# room_ind.net
KiCad netlist of a schematic drawn in EAGLE
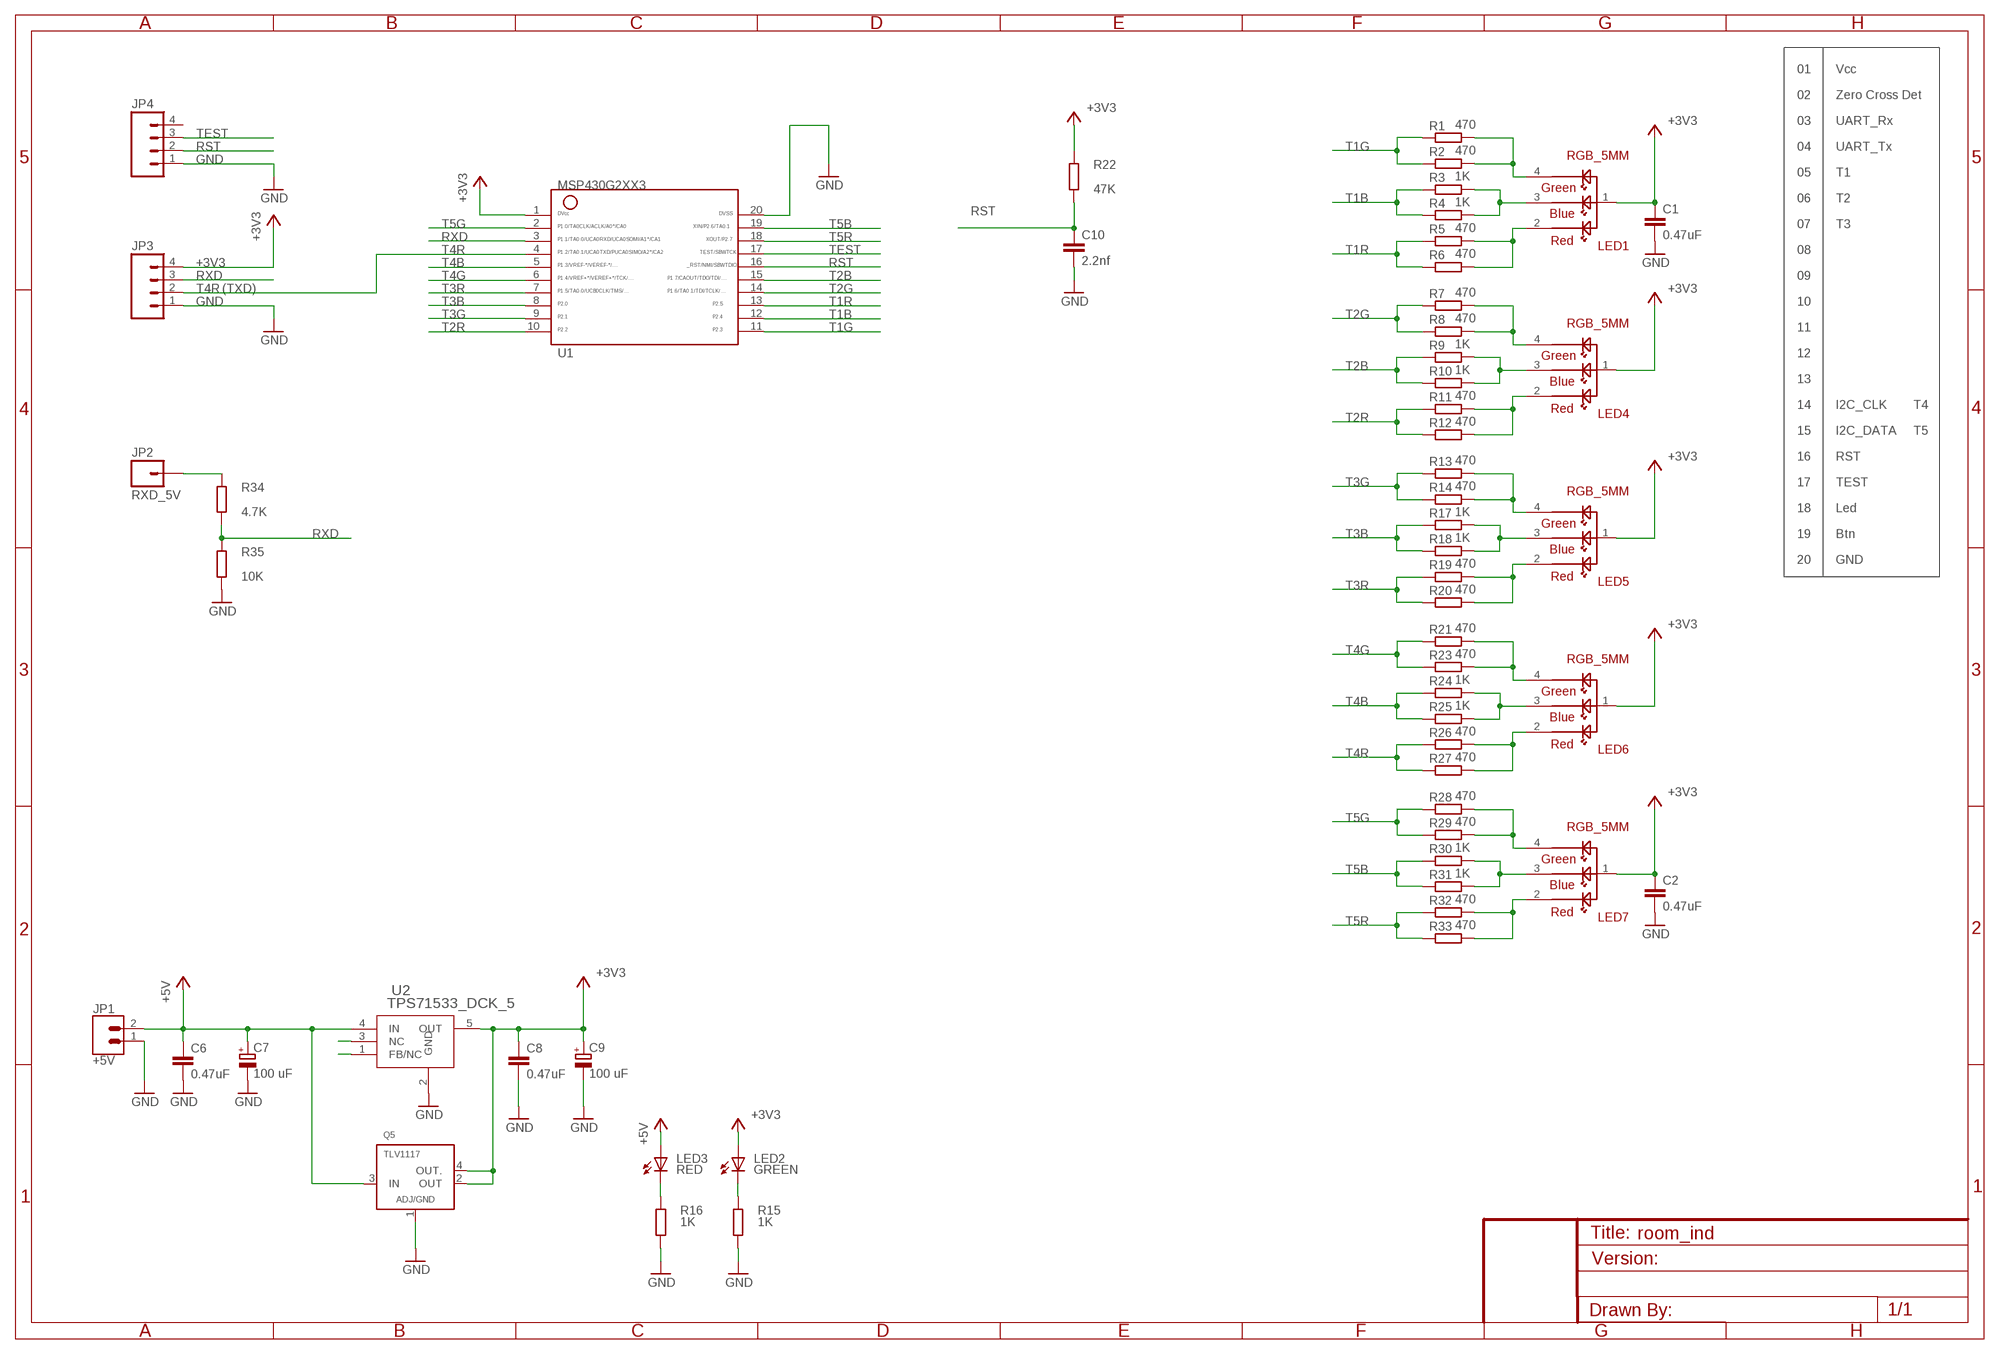
[diagram p0: schematic, sheet 1]

(export (version "E")
  (design (tool "Eeschema 10.0.6"))
  (components
    (comp (ref "C1")
      (value "0.47uF")
      (footprint "eagle-import:C0805")
      (libsource (lib "eagle-import") (part "C-EUC0805"))
    )
    (comp (ref "C2")
      (value "0.47uF")
      (footprint "eagle-import:C0805")
      (libsource (lib "eagle-import") (part "C-EUC0805"))
    )
    (comp (ref "C6")
      (value "0.47uF")
      (footprint "eagle-import:C0805")
      (libsource (lib "eagle-import") (part "C-EUC0805"))
    )
    (comp (ref "C7")
      (value "100 uF")
      (footprint "eagle-import:E2,5-7")
      (libsource (lib "eagle-import") (part "CPOL-EUE2.5-7"))
    )
    (comp (ref "C8")
      (value "0.47uF")
      (footprint "eagle-import:C0805")
      (libsource (lib "eagle-import") (part "C-EUC0805"))
    )
    (comp (ref "C9")
      (value "100 uF")
      (footprint "eagle-import:E2,5-7")
      (libsource (lib "eagle-import") (part "CPOL-EUE2.5-7"))
    )
    (comp (ref "C10")
      (value "2.2nf")
      (footprint "eagle-import:C0805")
      (libsource (lib "eagle-import") (part "C-EUC0805"))
    )
    (comp (ref "JP1")
      (value "+5V")
      (footprint "eagle-import:BLUE_TERM")
      (libsource (lib "eagle-import") (part "BLUE_TERM"))
    )
    (comp (ref "JP2")
      (value "RXD_5V")
      (footprint "eagle-import:1X01")
      (libsource (lib "eagle-import") (part "M01PTH"))
    )
    (comp (ref "JP3")
      (value "M04PTH")
      (footprint "eagle-import:1X04")
      (libsource (lib "eagle-import") (part "M04PTH"))
    )
    (comp (ref "JP4")
      (value "M04PTH")
      (footprint "eagle-import:1X04")
      (libsource (lib "eagle-import") (part "M04PTH"))
    )
    (comp (ref "LED1")
      (value "RGB_5MM")
      (footprint "eagle-import:RGB_5MM")
      (libsource (lib "eagle-import") (part "RGB_5MM"))
    )
    (comp (ref "LED2")
      (value "GREEN")
      (footprint "eagle-import:CHIP-LED0805")
      (libsource (lib "eagle-import") (part "LEDCHIP-LED0805"))
    )
    (comp (ref "LED3")
      (value "RED")
      (footprint "eagle-import:CHIP-LED0805")
      (libsource (lib "eagle-import") (part "LEDCHIP-LED0805"))
    )
    (comp (ref "LED4")
      (value "RGB_5MM")
      (footprint "eagle-import:RGB_5MM")
      (libsource (lib "eagle-import") (part "RGB_5MM"))
    )
    (comp (ref "LED5")
      (value "RGB_5MM")
      (footprint "eagle-import:RGB_5MM")
      (libsource (lib "eagle-import") (part "RGB_5MM"))
    )
    (comp (ref "LED6")
      (value "RGB_5MM")
      (footprint "eagle-import:RGB_5MM")
      (libsource (lib "eagle-import") (part "RGB_5MM"))
    )
    (comp (ref "LED7")
      (value "RGB_5MM")
      (footprint "eagle-import:RGB_5MM")
      (libsource (lib "eagle-import") (part "RGB_5MM"))
    )
    (comp (ref "Q5")
      (value "TLV1117")
      (footprint "eagle-import:SOT223-4")
      (libsource (lib "eagle-import") (part "TLV1117"))
    )
    (comp (ref "R1")
      (value "470")
      (footprint "eagle-import:R0805")
      (libsource (lib "eagle-import") (part "R-EU_R0805"))
    )
    (comp (ref "R2")
      (value "470")
      (footprint "eagle-import:0207_7")
      (libsource (lib "eagle-import") (part "R-EU_0207/7"))
    )
    (comp (ref "R3")
      (value "1K")
      (footprint "eagle-import:R0805")
      (libsource (lib "eagle-import") (part "R-EU_R0805"))
    )
    (comp (ref "R4")
      (value "1K")
      (footprint "eagle-import:0207_7")
      (libsource (lib "eagle-import") (part "R-EU_0207/7"))
    )
    (comp (ref "R5")
      (value "470")
      (footprint "eagle-import:R0805")
      (libsource (lib "eagle-import") (part "R-EU_R0805"))
    )
    (comp (ref "R6")
      (value "470")
      (footprint "eagle-import:0207_7")
      (libsource (lib "eagle-import") (part "R-EU_0207/7"))
    )
    (comp (ref "R7")
      (value "470")
      (footprint "eagle-import:R0805")
      (libsource (lib "eagle-import") (part "R-EU_R0805"))
    )
    (comp (ref "R8")
      (value "470")
      (footprint "eagle-import:0207_7")
      (libsource (lib "eagle-import") (part "R-EU_0207/7"))
    )
    (comp (ref "R9")
      (value "1K")
      (footprint "eagle-import:R0805")
      (libsource (lib "eagle-import") (part "R-EU_R0805"))
    )
    (comp (ref "R10")
      (value "1K")
      (footprint "eagle-import:0207_7")
      (libsource (lib "eagle-import") (part "R-EU_0207/7"))
    )
    (comp (ref "R11")
      (value "470")
      (footprint "eagle-import:R0805")
      (libsource (lib "eagle-import") (part "R-EU_R0805"))
    )
    (comp (ref "R12")
      (value "470")
      (footprint "eagle-import:0207_7")
      (libsource (lib "eagle-import") (part "R-EU_0207/7"))
    )
    (comp (ref "R13")
      (value "470")
      (footprint "eagle-import:R0805")
      (libsource (lib "eagle-import") (part "R-EU_R0805"))
    )
    (comp (ref "R14")
      (value "470")
      (footprint "eagle-import:0207_7")
      (libsource (lib "eagle-import") (part "R-EU_0207/7"))
    )
    (comp (ref "R15")
      (value "1K")
      (footprint "eagle-import:R0805")
      (libsource (lib "eagle-import") (part "R-EU_R0805"))
    )
    (comp (ref "R16")
      (value "1K")
      (footprint "eagle-import:R0805")
      (libsource (lib "eagle-import") (part "R-EU_R0805"))
    )
    (comp (ref "R17")
      (value "1K")
      (footprint "eagle-import:R0805")
      (libsource (lib "eagle-import") (part "R-EU_R0805"))
    )
    (comp (ref "R18")
      (value "1K")
      (footprint "eagle-import:0207_7")
      (libsource (lib "eagle-import") (part "R-EU_0207/7"))
    )
    (comp (ref "R19")
      (value "470")
      (footprint "eagle-import:R0805")
      (libsource (lib "eagle-import") (part "R-EU_R0805"))
    )
    (comp (ref "R20")
      (value "470")
      (footprint "eagle-import:0207_7")
      (libsource (lib "eagle-import") (part "R-EU_0207/7"))
    )
    (comp (ref "R21")
      (value "470")
      (footprint "eagle-import:R0805")
      (libsource (lib "eagle-import") (part "R-EU_R0805"))
    )
    (comp (ref "R22")
      (value "47K")
      (footprint "eagle-import:R0805")
      (libsource (lib "eagle-import") (part "R-EU_R0805"))
    )
    (comp (ref "R23")
      (value "470")
      (footprint "eagle-import:0207_7")
      (libsource (lib "eagle-import") (part "R-EU_0207/7"))
    )
    (comp (ref "R24")
      (value "1K")
      (footprint "eagle-import:R0805")
      (libsource (lib "eagle-import") (part "R-EU_R0805"))
    )
    (comp (ref "R25")
      (value "1K")
      (footprint "eagle-import:0207_7")
      (libsource (lib "eagle-import") (part "R-EU_0207/7"))
    )
    (comp (ref "R26")
      (value "470")
      (footprint "eagle-import:R0805")
      (libsource (lib "eagle-import") (part "R-EU_R0805"))
    )
    (comp (ref "R27")
      (value "470")
      (footprint "eagle-import:0207_7")
      (libsource (lib "eagle-import") (part "R-EU_0207/7"))
    )
    (comp (ref "R28")
      (value "470")
      (footprint "eagle-import:R0805")
      (libsource (lib "eagle-import") (part "R-EU_R0805"))
    )
    (comp (ref "R29")
      (value "470")
      (footprint "eagle-import:0207_7")
      (libsource (lib "eagle-import") (part "R-EU_0207/7"))
    )
    (comp (ref "R30")
      (value "1K")
      (footprint "eagle-import:R0805")
      (libsource (lib "eagle-import") (part "R-EU_R0805"))
    )
    (comp (ref "R31")
      (value "1K")
      (footprint "eagle-import:0207_7")
      (libsource (lib "eagle-import") (part "R-EU_0207/7"))
    )
    (comp (ref "R32")
      (value "470")
      (footprint "eagle-import:R0805")
      (libsource (lib "eagle-import") (part "R-EU_R0805"))
    )
    (comp (ref "R33")
      (value "470")
      (footprint "eagle-import:0207_7")
      (libsource (lib "eagle-import") (part "R-EU_0207/7"))
    )
    (comp (ref "R34")
      (value "4.7K")
      (footprint "eagle-import:R0805")
      (libsource (lib "eagle-import") (part "R-EU_R0805"))
    )
    (comp (ref "R35")
      (value "10K")
      (footprint "eagle-import:R0805")
      (libsource (lib "eagle-import") (part "R-EU_R0805"))
    )
    (comp (ref "U1")
      (value "G2XX3---PW20")
      (footprint "eagle-import:PW20")
      (libsource (lib "eagle-import") (part "G2XX3---PW20"))
    )
    (comp (ref "U2")
      (value "TPS71533_DCK_5")
      (footprint "eagle-import:DCK5")
      (fields
        (field (name "GENERIC_PART_NUMBER") "TPS71533")
        (field (name "MANUFACTURER") "Texas Instruments")
        (field (name "MANUFACTURER_PART_NUMBER") "tps71533_dck_5")
      )
      (libsource (lib "eagle-import") (part "TPS71533_DCK_5"))
    )
  )
  (nets
    (net (code "1") (name "+3V3") (class "Default")
      (node (ref "C1") (pin "1") (pinfunction "1_1") (pintype "passive"))
      (node (ref "C2") (pin "1") (pinfunction "1_1") (pintype "passive"))
      (node (ref "C8") (pin "1") (pinfunction "1_1") (pintype "passive"))
      (node (ref "C9") (pin "+") (pinfunction "+_+") (pintype "passive"))
      (node (ref "JP3") (pin "4") (pinfunction "4_4") (pintype "passive"))
      (node (ref "LED1") (pin "1") (pinfunction "1_1") (pintype "bidirectional"))
      (node (ref "LED2") (pin "A") (pinfunction "A_A") (pintype "passive"))
      (node (ref "LED4") (pin "1") (pinfunction "1_1") (pintype "bidirectional"))
      (node (ref "LED5") (pin "1") (pinfunction "1_1") (pintype "bidirectional"))
      (node (ref "LED6") (pin "1") (pinfunction "1_1") (pintype "bidirectional"))
      (node (ref "LED7") (pin "1") (pinfunction "1_1") (pintype "bidirectional"))
      (node (ref "Q5") (pin "2") (pinfunction "OUT_2") (pintype "power_in"))
      (node (ref "Q5") (pin "4") (pinfunction "OUT._4") (pintype "power_in"))
      (node (ref "R22") (pin "2") (pinfunction "2_2") (pintype "passive"))
      (node (ref "U1") (pin "1") (pinfunction "1_1") (pintype "bidirectional"))
      (node (ref "U2") (pin "5") (pinfunction "OUT_5") (pintype "power_in"))
    )
    (net (code "2") (name "+5V") (class "Default")
      (node (ref "C6") (pin "1") (pinfunction "1_1") (pintype "passive"))
      (node (ref "C7") (pin "+") (pinfunction "+_+") (pintype "passive"))
      (node (ref "JP1") (pin "2") (pinfunction "2_2") (pintype "passive"))
      (node (ref "LED3") (pin "A") (pinfunction "A_A") (pintype "passive"))
      (node (ref "Q5") (pin "3") (pinfunction "IN_3") (pintype "power_in"))
      (node (ref "U2") (pin "4") (pinfunction "IN_4") (pintype "power_in"))
    )
    (net (code "3") (name "/RST") (class "Default")
      (node (ref "C10") (pin "1") (pinfunction "1_1") (pintype "passive"))
      (node (ref "JP4") (pin "2") (pinfunction "2_2") (pintype "passive"))
      (node (ref "R22") (pin "1") (pinfunction "1_1") (pintype "passive"))
      (node (ref "U1") (pin "16") (pinfunction "16_16") (pintype "bidirectional"))
    )
    (net (code "4") (name "/RXD") (class "Default")
      (node (ref "JP3") (pin "3") (pinfunction "3_3") (pintype "passive"))
      (node (ref "R34") (pin "1") (pinfunction "1_1") (pintype "passive"))
      (node (ref "R35") (pin "2") (pinfunction "2_2") (pintype "passive"))
      (node (ref "U1") (pin "3") (pinfunction "3_3") (pintype "bidirectional"))
    )
    (net (code "5") (name "/T1B") (class "Default")
      (node (ref "R3") (pin "1") (pinfunction "1_1") (pintype "passive"))
      (node (ref "R4") (pin "1") (pinfunction "1_1") (pintype "passive"))
      (node (ref "U1") (pin "12") (pinfunction "12_12") (pintype "bidirectional"))
    )
    (net (code "6") (name "/T1G") (class "Default")
      (node (ref "R1") (pin "1") (pinfunction "1_1") (pintype "passive"))
      (node (ref "R2") (pin "1") (pinfunction "1_1") (pintype "passive"))
      (node (ref "U1") (pin "11") (pinfunction "11_11") (pintype "bidirectional"))
    )
    (net (code "7") (name "/T1R") (class "Default")
      (node (ref "R5") (pin "1") (pinfunction "1_1") (pintype "passive"))
      (node (ref "R6") (pin "1") (pinfunction "1_1") (pintype "passive"))
      (node (ref "U1") (pin "13") (pinfunction "13_13") (pintype "bidirectional"))
    )
    (net (code "8") (name "/T2B") (class "Default")
      (node (ref "R10") (pin "1") (pinfunction "1_1") (pintype "passive"))
      (node (ref "R9") (pin "1") (pinfunction "1_1") (pintype "passive"))
      (node (ref "U1") (pin "15") (pinfunction "15_15") (pintype "bidirectional"))
    )
    (net (code "9") (name "/T2G") (class "Default")
      (node (ref "R7") (pin "1") (pinfunction "1_1") (pintype "passive"))
      (node (ref "R8") (pin "1") (pinfunction "1_1") (pintype "passive"))
      (node (ref "U1") (pin "14") (pinfunction "14_14") (pintype "bidirectional"))
    )
    (net (code "10") (name "/T2R") (class "Default")
      (node (ref "R11") (pin "1") (pinfunction "1_1") (pintype "passive"))
      (node (ref "R12") (pin "1") (pinfunction "1_1") (pintype "passive"))
      (node (ref "U1") (pin "10") (pinfunction "10_10") (pintype "bidirectional"))
    )
    (net (code "11") (name "/T3B") (class "Default")
      (node (ref "R17") (pin "1") (pinfunction "1_1") (pintype "passive"))
      (node (ref "R18") (pin "1") (pinfunction "1_1") (pintype "passive"))
      (node (ref "U1") (pin "8") (pinfunction "8_8") (pintype "bidirectional"))
    )
    (net (code "12") (name "/T3G") (class "Default")
      (node (ref "R13") (pin "1") (pinfunction "1_1") (pintype "passive"))
      (node (ref "R14") (pin "1") (pinfunction "1_1") (pintype "passive"))
      (node (ref "U1") (pin "9") (pinfunction "9_9") (pintype "bidirectional"))
    )
    (net (code "13") (name "/T3R") (class "Default")
      (node (ref "R19") (pin "1") (pinfunction "1_1") (pintype "passive"))
      (node (ref "R20") (pin "1") (pinfunction "1_1") (pintype "passive"))
      (node (ref "U1") (pin "7") (pinfunction "7_7") (pintype "bidirectional"))
    )
    (net (code "14") (name "/T4B") (class "Default")
      (node (ref "R24") (pin "1") (pinfunction "1_1") (pintype "passive"))
      (node (ref "R25") (pin "1") (pinfunction "1_1") (pintype "passive"))
      (node (ref "U1") (pin "5") (pinfunction "5_5") (pintype "bidirectional"))
    )
    (net (code "15") (name "/T4G") (class "Default")
      (node (ref "R21") (pin "1") (pinfunction "1_1") (pintype "passive"))
      (node (ref "R23") (pin "1") (pinfunction "1_1") (pintype "passive"))
      (node (ref "U1") (pin "6") (pinfunction "6_6") (pintype "bidirectional"))
    )
    (net (code "16") (name "/T4R") (class "Default")
      (node (ref "JP3") (pin "2") (pinfunction "2_2") (pintype "passive"))
      (node (ref "R26") (pin "1") (pinfunction "1_1") (pintype "passive"))
      (node (ref "R27") (pin "1") (pinfunction "1_1") (pintype "passive"))
      (node (ref "U1") (pin "4") (pinfunction "4_4") (pintype "bidirectional"))
    )
    (net (code "17") (name "/T5B") (class "Default")
      (node (ref "R30") (pin "1") (pinfunction "1_1") (pintype "passive"))
      (node (ref "R31") (pin "1") (pinfunction "1_1") (pintype "passive"))
      (node (ref "U1") (pin "19") (pinfunction "19_19") (pintype "bidirectional"))
    )
    (net (code "18") (name "/T5G") (class "Default")
      (node (ref "R28") (pin "1") (pinfunction "1_1") (pintype "passive"))
      (node (ref "R29") (pin "1") (pinfunction "1_1") (pintype "passive"))
      (node (ref "U1") (pin "2") (pinfunction "2_2") (pintype "bidirectional"))
    )
    (net (code "19") (name "/T5R") (class "Default")
      (node (ref "R32") (pin "1") (pinfunction "1_1") (pintype "passive"))
      (node (ref "R33") (pin "1") (pinfunction "1_1") (pintype "passive"))
      (node (ref "U1") (pin "18") (pinfunction "18_18") (pintype "bidirectional"))
    )
    (net (code "20") (name "/TEST") (class "Default")
      (node (ref "JP4") (pin "3") (pinfunction "3_3") (pintype "passive"))
      (node (ref "U1") (pin "17") (pinfunction "17_17") (pintype "bidirectional"))
    )
    (net (code "21") (name "GND") (class "Default")
      (node (ref "C1") (pin "2") (pinfunction "2_2") (pintype "passive"))
      (node (ref "C10") (pin "2") (pinfunction "2_2") (pintype "passive"))
      (node (ref "C2") (pin "2") (pinfunction "2_2") (pintype "passive"))
      (node (ref "C6") (pin "2") (pinfunction "2_2") (pintype "passive"))
      (node (ref "C7") (pin "-") (pinfunction "-_-") (pintype "passive"))
      (node (ref "C8") (pin "2") (pinfunction "2_2") (pintype "passive"))
      (node (ref "C9") (pin "-") (pinfunction "-_-") (pintype "passive"))
      (node (ref "JP1") (pin "1") (pinfunction "1_1") (pintype "passive"))
      (node (ref "JP3") (pin "1") (pinfunction "1_1") (pintype "passive"))
      (node (ref "JP4") (pin "1") (pinfunction "1_1") (pintype "passive"))
      (node (ref "Q5") (pin "1") (pinfunction "ADJ/GND_1") (pintype "bidirectional"))
      (node (ref "R15") (pin "1") (pinfunction "1_1") (pintype "passive"))
      (node (ref "R16") (pin "1") (pinfunction "1_1") (pintype "passive"))
      (node (ref "R35") (pin "1") (pinfunction "1_1") (pintype "passive"))
      (node (ref "U1") (pin "20") (pinfunction "20_20") (pintype "bidirectional"))
      (node (ref "U2") (pin "2") (pinfunction "GND_2") (pintype "power_in"))
    )
    (net (code "22") (name "Net-(JP2-Pad1)") (class "Default")
      (node (ref "JP2") (pin "1") (pinfunction "1_1") (pintype "passive"))
      (node (ref "R34") (pin "2") (pinfunction "2_2") (pintype "passive"))
    )
    (net (code "23") (name "Net-(LED1-Pad2)") (class "Default")
      (node (ref "LED1") (pin "2") (pinfunction "2_2") (pintype "bidirectional"))
      (node (ref "R5") (pin "2") (pinfunction "2_2") (pintype "passive"))
      (node (ref "R6") (pin "2") (pinfunction "2_2") (pintype "passive"))
    )
    (net (code "24") (name "Net-(LED1-Pad3)") (class "Default")
      (node (ref "LED1") (pin "3") (pinfunction "3_3") (pintype "bidirectional"))
      (node (ref "R3") (pin "2") (pinfunction "2_2") (pintype "passive"))
      (node (ref "R4") (pin "2") (pinfunction "2_2") (pintype "passive"))
    )
    (net (code "25") (name "Net-(LED1-Pad4)") (class "Default")
      (node (ref "LED1") (pin "4") (pinfunction "4_4") (pintype "bidirectional"))
      (node (ref "R1") (pin "2") (pinfunction "2_2") (pintype "passive"))
      (node (ref "R2") (pin "2") (pinfunction "2_2") (pintype "passive"))
    )
    (net (code "26") (name "Net-(LED2-PadC)") (class "Default")
      (node (ref "LED2") (pin "C") (pinfunction "C_C") (pintype "passive"))
      (node (ref "R15") (pin "2") (pinfunction "2_2") (pintype "passive"))
    )
    (net (code "27") (name "Net-(LED3-PadC)") (class "Default")
      (node (ref "LED3") (pin "C") (pinfunction "C_C") (pintype "passive"))
      (node (ref "R16") (pin "2") (pinfunction "2_2") (pintype "passive"))
    )
    (net (code "28") (name "Net-(LED4-Pad2)") (class "Default")
      (node (ref "LED4") (pin "2") (pinfunction "2_2") (pintype "bidirectional"))
      (node (ref "R11") (pin "2") (pinfunction "2_2") (pintype "passive"))
      (node (ref "R12") (pin "2") (pinfunction "2_2") (pintype "passive"))
    )
    (net (code "29") (name "Net-(LED4-Pad3)") (class "Default")
      (node (ref "LED4") (pin "3") (pinfunction "3_3") (pintype "bidirectional"))
      (node (ref "R10") (pin "2") (pinfunction "2_2") (pintype "passive"))
      (node (ref "R9") (pin "2") (pinfunction "2_2") (pintype "passive"))
    )
    (net (code "30") (name "Net-(LED4-Pad4)") (class "Default")
      (node (ref "LED4") (pin "4") (pinfunction "4_4") (pintype "bidirectional"))
      (node (ref "R7") (pin "2") (pinfunction "2_2") (pintype "passive"))
      (node (ref "R8") (pin "2") (pinfunction "2_2") (pintype "passive"))
    )
    (net (code "31") (name "Net-(LED5-Pad2)") (class "Default")
      (node (ref "LED5") (pin "2") (pinfunction "2_2") (pintype "bidirectional"))
      (node (ref "R19") (pin "2") (pinfunction "2_2") (pintype "passive"))
      (node (ref "R20") (pin "2") (pinfunction "2_2") (pintype "passive"))
    )
    (net (code "32") (name "Net-(LED5-Pad3)") (class "Default")
      (node (ref "LED5") (pin "3") (pinfunction "3_3") (pintype "bidirectional"))
      (node (ref "R17") (pin "2") (pinfunction "2_2") (pintype "passive"))
      (node (ref "R18") (pin "2") (pinfunction "2_2") (pintype "passive"))
    )
    (net (code "33") (name "Net-(LED5-Pad4)") (class "Default")
      (node (ref "LED5") (pin "4") (pinfunction "4_4") (pintype "bidirectional"))
      (node (ref "R13") (pin "2") (pinfunction "2_2") (pintype "passive"))
      (node (ref "R14") (pin "2") (pinfunction "2_2") (pintype "passive"))
    )
    (net (code "34") (name "Net-(LED6-Pad2)") (class "Default")
      (node (ref "LED6") (pin "2") (pinfunction "2_2") (pintype "bidirectional"))
      (node (ref "R26") (pin "2") (pinfunction "2_2") (pintype "passive"))
      (node (ref "R27") (pin "2") (pinfunction "2_2") (pintype "passive"))
    )
    (net (code "35") (name "Net-(LED6-Pad3)") (class "Default")
      (node (ref "LED6") (pin "3") (pinfunction "3_3") (pintype "bidirectional"))
      (node (ref "R24") (pin "2") (pinfunction "2_2") (pintype "passive"))
      (node (ref "R25") (pin "2") (pinfunction "2_2") (pintype "passive"))
    )
    (net (code "36") (name "Net-(LED6-Pad4)") (class "Default")
      (node (ref "LED6") (pin "4") (pinfunction "4_4") (pintype "bidirectional"))
      (node (ref "R21") (pin "2") (pinfunction "2_2") (pintype "passive"))
      (node (ref "R23") (pin "2") (pinfunction "2_2") (pintype "passive"))
    )
    (net (code "37") (name "Net-(LED7-Pad2)") (class "Default")
      (node (ref "LED7") (pin "2") (pinfunction "2_2") (pintype "bidirectional"))
      (node (ref "R32") (pin "2") (pinfunction "2_2") (pintype "passive"))
      (node (ref "R33") (pin "2") (pinfunction "2_2") (pintype "passive"))
    )
    (net (code "38") (name "Net-(LED7-Pad3)") (class "Default")
      (node (ref "LED7") (pin "3") (pinfunction "3_3") (pintype "bidirectional"))
      (node (ref "R30") (pin "2") (pinfunction "2_2") (pintype "passive"))
      (node (ref "R31") (pin "2") (pinfunction "2_2") (pintype "passive"))
    )
    (net (code "39") (name "Net-(LED7-Pad4)") (class "Default")
      (node (ref "LED7") (pin "4") (pinfunction "4_4") (pintype "bidirectional"))
      (node (ref "R28") (pin "2") (pinfunction "2_2") (pintype "passive"))
      (node (ref "R29") (pin "2") (pinfunction "2_2") (pintype "passive"))
    )
    (net (code "40") (name "unconnected-(JP4-Pad4)") (class "Default")
      (node (ref "JP4") (pin "4") (pinfunction "4_4") (pintype "passive"))
    )
    (net (code "41") (name "unconnected-(U2-FB{slash}NC-Pad1)") (class "Default")
      (node (ref "U2") (pin "1") (pinfunction "FB/NC_1") (pintype "input"))
    )
    (net (code "42") (name "unconnected-(U2-NC-Pad3)") (class "Default")
      (node (ref "U2") (pin "3") (pinfunction "NC_3") (pintype "no_connect"))
    )
  )
)
